# main.net
KiCad netlist of a schematic drawn in Altium Designer
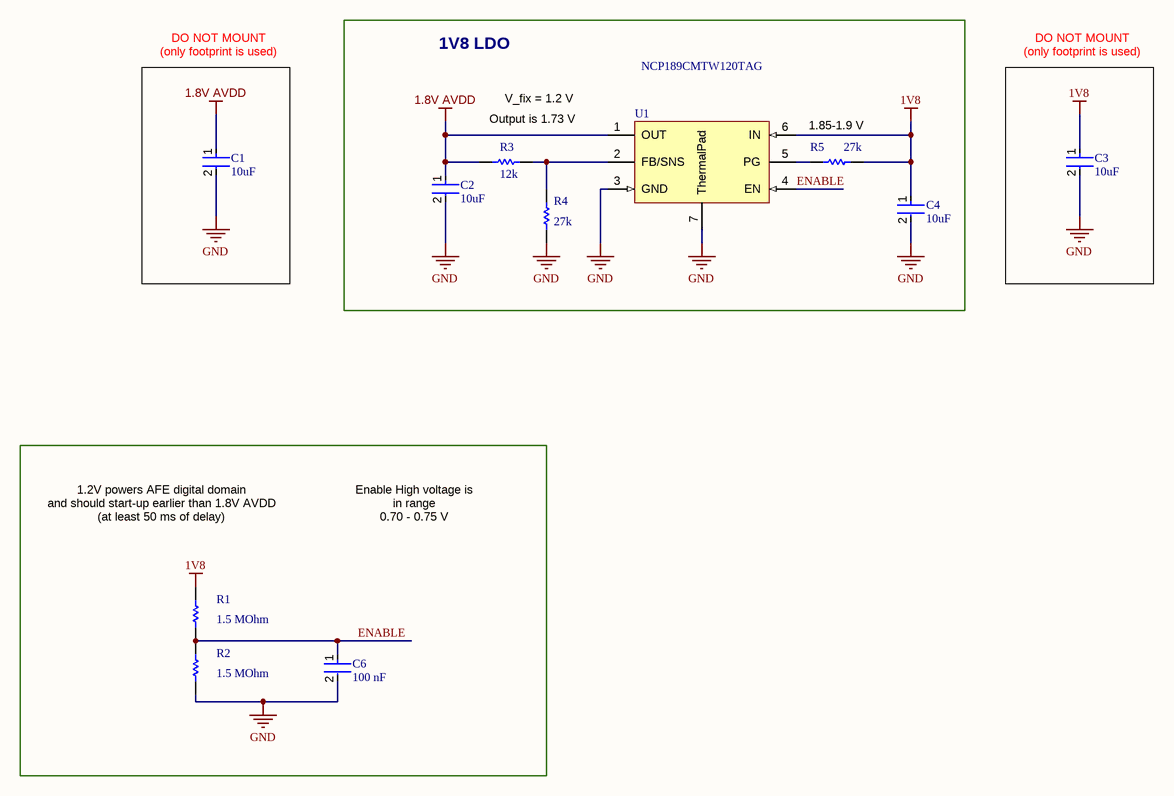
[diagram p0: main.SchDoc]

(export (version "E")
  (design (tool "Eeschema 10.0.6"))
  (components
    (comp (ref "C1")
      (value "10uF")
      (footprint "FP-GRM188-0_1-e0_2_0_55-IPC_A")
      (description "Chip Multilayer Ceramic Capacitors for General Purpose, 0603, 10uF, X5R, 15%, 20%, 6.3V")
      (fields (field (name "VOLTAGE") "6.3V") (field (name "TOLERANCE") "20%"))
      (libsource (lib "Altium Content Vault") (part "02cd4be3c70576c341d710602a673aa"))
    )
    (comp (ref "C2")
      (value "10uF")
      (footprint "FP-GRM188-0_1-e0_2_0_55-IPC_A")
      (description "Chip Multilayer Ceramic Capacitors for General Purpose, 0603, 10uF, X5R, 15%, 20%, 6.3V")
      (fields (field (name "VOLTAGE") "6.3V") (field (name "TOLERANCE") "20%"))
      (libsource (lib "Altium Content Vault") (part "02cd4be3c70576c341d710602a673aa"))
    )
    (comp (ref "C3")
      (value "10uF")
      (footprint "FP-GRM188-0_1-e0_2_0_55-IPC_A")
      (description "Chip Multilayer Ceramic Capacitors for General Purpose, 0603, 10uF, X5R, 15%, 20%, 6.3V")
      (fields (field (name "VOLTAGE") "6.3V") (field (name "TOLERANCE") "20%"))
      (libsource (lib "Altium Content Vault") (part "02cd4be3c70576c341d710602a673aa"))
    )
    (comp (ref "C4")
      (value "10uF")
      (footprint "FP-GRM188-0_1-e0_2_0_55-IPC_A")
      (description "Chip Multilayer Ceramic Capacitors for General Purpose, 0603, 10uF, X5R, 15%, 20%, 6.3V")
      (fields (field (name "VOLTAGE") "6.3V") (field (name "TOLERANCE") "20%"))
      (libsource (lib "Altium Content Vault") (part "02cd4be3c70576c341d710602a673aa"))
    )
    (comp (ref "C6")
      (value "100 nF")
      (footprint "FP-C0402-BB-MFG")
      (description "CAP CER 0.1UF 10V X5R 0402\r\nC0402C104K8PACTU")
      (fields (field (name "MANUFACTURER") "Kemet") (field (name "TOLERANCE") "0.1"))
      (libsource (lib "Altium Content Vault") (part "b4654b650e69147ec39a6b967a45e02"))
    )
    (comp (ref "R1")
      (value "1.5 MOhm")
      (footprint "RESC1005X40X25NL05T10")
      (description "RC0402FR-071M5L")
      (fields (field (name "MANUFACTURER") "Yageo / Phycomp"))
      (libsource (lib "Altium Content Vault") (part "RES"))
    )
    (comp (ref "R2")
      (value "1.5 MOhm")
      (footprint "RESC1005X40X25NL05T10")
      (description "RC0402FR-071M5L")
      (fields (field (name "MANUFACTURER") "Yageo / Phycomp"))
      (libsource (lib "Altium Content Vault") (part "RES"))
    )
    (comp (ref "R3")
      (value "12k")
      (footprint "RESC1005X40X25LL05T05")
      (description "ERJ-2RKF1202X")
      (fields (field (name "TOLERANCE") "1%"))
      (libsource (lib "Altium Content Vault") (part "RES-2"))
    )
    (comp (ref "R4")
      (value "27k")
      (footprint "RESC1005X40X25LL10T10")
      (description "ERA-2AEB273X")
      (fields (field (name "MANUFACTURER") "Panasonic"))
      (libsource (lib "Altium Content Vault") (part "RES"))
    )
    (comp (ref "R5")
      (value "27k")
      (footprint "RESC1005X40X25LL10T10")
      (description "ERA-2AEB273X")
      (fields (field (name "MANUFACTURER") "Panasonic"))
      (libsource (lib "Altium Content Vault") (part "RES"))
    )
    (comp (ref "U1")
      (value "NCP189CMTW120TAG")
      (footprint "power_board_evm:NCP189")
      (libsource (lib "power_board_evm") (part "NCP189CMTW120TAG"))
    )
  )
  (nets
    (net (code "1") (name "/ENABLE") (class "Default")
      (node (ref "C6") (pin "1") (pinfunction "1_1") (pintype "passive"))
      (node (ref "R1") (pin "1") (pinfunction "1_1") (pintype "passive"))
      (node (ref "R2") (pin "2") (pinfunction "2_2") (pintype "passive"))
      (node (ref "U1") (pin "4") (pinfunction "EN_4") (pintype "input"))
    )
    (net (code "2") (name "1.8V AVDD") (class "Default")
      (node (ref "C1") (pin "1") (pinfunction "1_1") (pintype "passive"))
      (node (ref "C2") (pin "1") (pinfunction "1_1") (pintype "passive"))
      (node (ref "R3") (pin "1") (pinfunction "1_1") (pintype "passive"))
      (node (ref "U1") (pin "1") (pinfunction "OUT_1") (pintype "power_in"))
    )
    (net (code "3") (name "1V8") (class "Default")
      (node (ref "C3") (pin "1") (pinfunction "1_1") (pintype "passive"))
      (node (ref "C4") (pin "1") (pinfunction "1_1") (pintype "passive"))
      (node (ref "R1") (pin "2") (pinfunction "2_2") (pintype "passive"))
      (node (ref "R5") (pin "1") (pinfunction "1_1") (pintype "passive"))
      (node (ref "U1") (pin "6") (pinfunction "IN_6") (pintype "input"))
    )
    (net (code "4") (name "GND") (class "Default")
      (node (ref "C1") (pin "2") (pinfunction "2_2") (pintype "passive"))
      (node (ref "C2") (pin "2") (pinfunction "2_2") (pintype "passive"))
      (node (ref "C3") (pin "2") (pinfunction "2_2") (pintype "passive"))
      (node (ref "C4") (pin "2") (pinfunction "2_2") (pintype "passive"))
      (node (ref "C6") (pin "2") (pinfunction "2_2") (pintype "passive"))
      (node (ref "R2") (pin "1") (pinfunction "1_1") (pintype "passive"))
      (node (ref "R4") (pin "1") (pinfunction "1_1") (pintype "passive"))
      (node (ref "U1") (pin "3") (pinfunction "GND_3") (pintype "input"))
      (node (ref "U1") (pin "7") (pinfunction "ThermalPad_7") (pintype "power_in"))
    )
    (net (code "5") (name "Net-(U1-FB{slash}SNS)") (class "Default")
      (node (ref "R3") (pin "2") (pinfunction "2_2") (pintype "passive"))
      (node (ref "R4") (pin "2") (pinfunction "2_2") (pintype "passive"))
      (node (ref "U1") (pin "2") (pinfunction "FB/SNS_2") (pintype "passive"))
    )
    (net (code "6") (name "Net-(U1-PG)") (class "Default")
      (node (ref "R5") (pin "2") (pinfunction "2_2") (pintype "passive"))
      (node (ref "U1") (pin "5") (pinfunction "PG_5") (pintype "power_in"))
    )
  )
)
